# BSPD_5_Hank.net
KiCad netlist of a schematic drawn in EAGLE
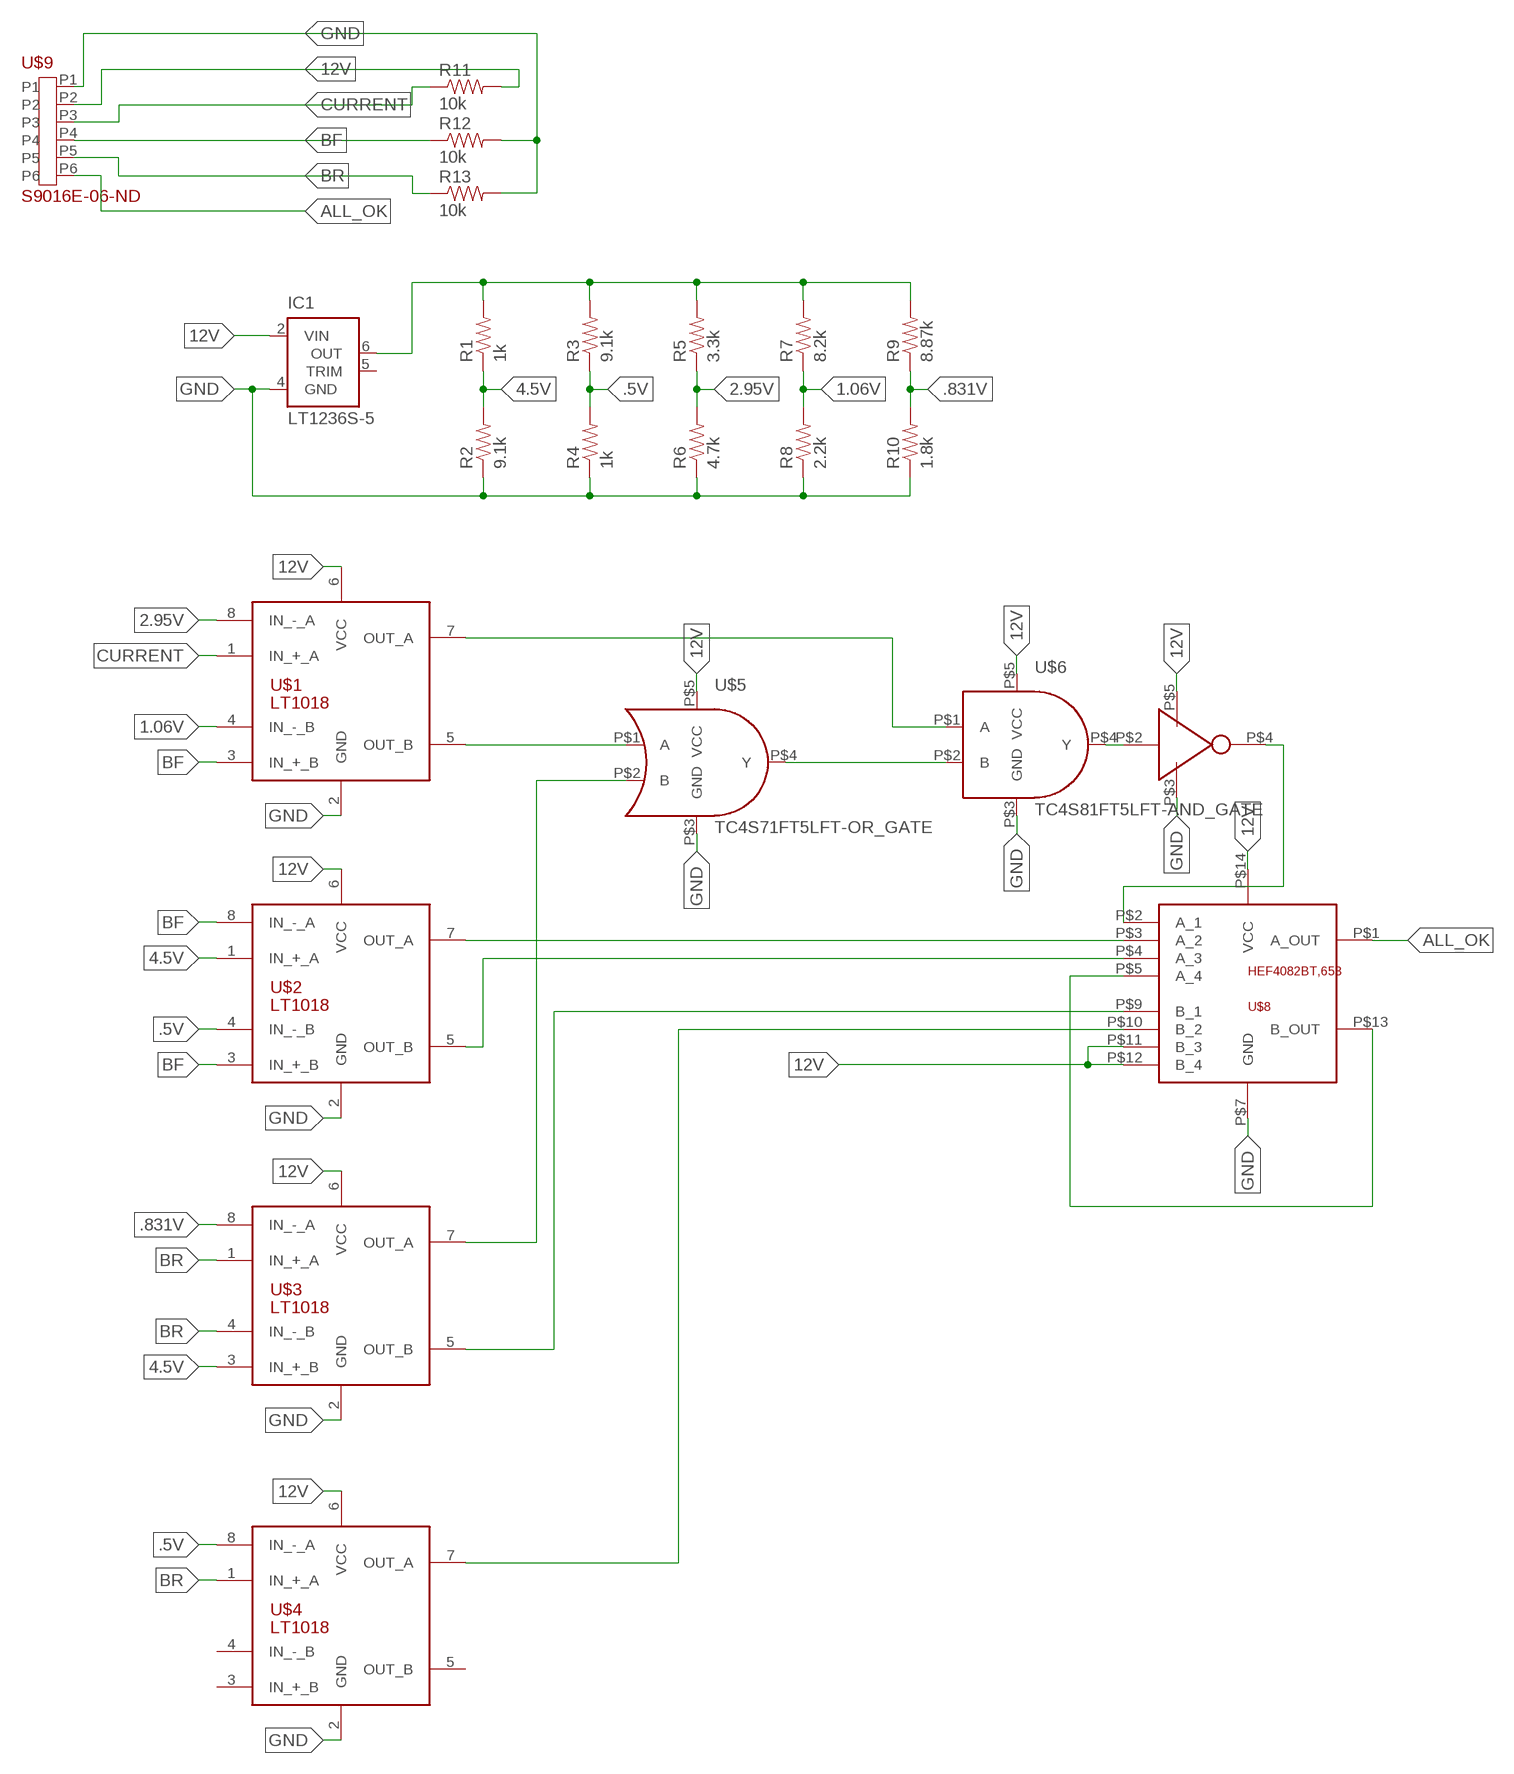
[diagram p0: schematic, sheet 1]

(export (version "E")
  (design (tool "Eeschema 10.0.6"))
  (components
    (comp (ref "IC1")
      (value "LT1236S-5")
      (footprint "eagle-import:SOIC8")
      (libsource (lib "eagle-import") (part "LT1236?S-5"))
    )
    (comp (ref "R1")
      (value "1k")
      (footprint "eagle-import:0603-RES")
      (libsource (lib "eagle-import") (part "RESISTOR0603"))
    )
    (comp (ref "R2")
      (value "9.1k")
      (footprint "eagle-import:0603-RES")
      (libsource (lib "eagle-import") (part "RESISTOR0603"))
    )
    (comp (ref "R3")
      (value "9.1k")
      (footprint "eagle-import:0603-RES")
      (libsource (lib "eagle-import") (part "RESISTOR0603"))
    )
    (comp (ref "R4")
      (value "1k")
      (footprint "eagle-import:0603-RES")
      (libsource (lib "eagle-import") (part "RESISTOR0603"))
    )
    (comp (ref "R5")
      (value "3.3k")
      (footprint "eagle-import:0603-RES")
      (libsource (lib "eagle-import") (part "RESISTOR0603"))
    )
    (comp (ref "R6")
      (value "4.7k")
      (footprint "eagle-import:0603-RES")
      (libsource (lib "eagle-import") (part "RESISTOR0603"))
    )
    (comp (ref "R7")
      (value "8.2k")
      (footprint "eagle-import:0603-RES")
      (libsource (lib "eagle-import") (part "RESISTOR0603"))
    )
    (comp (ref "R8")
      (value "2.2k")
      (footprint "eagle-import:0603-RES")
      (libsource (lib "eagle-import") (part "RESISTOR0603"))
    )
    (comp (ref "R9")
      (value "8.87k")
      (footprint "eagle-import:0603-RES")
      (libsource (lib "eagle-import") (part "RESISTOR0603"))
    )
    (comp (ref "R10")
      (value "1.8k")
      (footprint "eagle-import:0603-RES")
      (libsource (lib "eagle-import") (part "RESISTOR0603"))
    )
    (comp (ref "R11")
      (value "10k")
      (footprint "eagle-import:0603-RES")
      (libsource (lib "eagle-import") (part "RESISTOR0603"))
    )
    (comp (ref "R12")
      (value "10k")
      (footprint "eagle-import:0603-RES")
      (libsource (lib "eagle-import") (part "RESISTOR0603"))
    )
    (comp (ref "R13")
      (value "10k")
      (footprint "eagle-import:0603-RES")
      (libsource (lib "eagle-import") (part "RESISTOR0603"))
    )
    (comp (ref "U$1")
      (value "LT1018")
      (footprint "eagle-import:SOIC8")
      (libsource (lib "eagle-import") (part "LT1018"))
    )
    (comp (ref "U$2")
      (value "LT1018")
      (footprint "eagle-import:SOIC8")
      (libsource (lib "eagle-import") (part "LT1018"))
    )
    (comp (ref "U$3")
      (value "LT1018")
      (footprint "eagle-import:SOIC8")
      (libsource (lib "eagle-import") (part "LT1018"))
    )
    (comp (ref "U$4")
      (value "LT1018")
      (footprint "eagle-import:SOIC8")
      (libsource (lib "eagle-import") (part "LT1018"))
    )
    (comp (ref "U$5")
      (value "TC4S71FT5LFT-OR_GATE")
      (footprint "eagle-import:SSOP5-P-0.95")
      (libsource (lib "eagle-import") (part "TC4S71FT5LFT-OR_GATE"))
    )
    (comp (ref "U$6")
      (value "TC4S81FT5LFT-AND_GATE")
      (footprint "eagle-import:SSOP5-P-0.95")
      (libsource (lib "eagle-import") (part "TC4S81FT5LFT-AND_GATE"))
    )
    (comp (ref "U$7")
      (value "TC4S69F(TE85L,F)")
      (footprint "eagle-import:SSOP5-P-0.95")
      (libsource (lib "eagle-import") (part "TC4S69F(TE85L,F)"))
    )
    (comp (ref "U$8")
      (value "HEF4082BT,653")
      (footprint "eagle-import:NXP_14_SOIC")
      (libsource (lib "eagle-import") (part "HEF4082BT,653"))
    )
    (comp (ref "U$9")
      (value "S9016E-06-ND")
      (footprint "eagle-import:S9016E-05-ND")
      (libsource (lib "eagle-import") (part "S9016E-06-ND"))
    )
  )
  (nets
    (net (code "1") (name ".5V") (class "Default")
      (node (ref "R3") (pin "1") (pinfunction "1_1") (pintype "passive"))
      (node (ref "R4") (pin "2") (pinfunction "2_2") (pintype "passive"))
      (node (ref "U$2") (pin "4") (pinfunction "IN_-_B_4") (pintype "input"))
      (node (ref "U$4") (pin "8") (pinfunction "IN_-_A_8") (pintype "input"))
    )
    (net (code "2") (name ".831V") (class "Default")
      (node (ref "R10") (pin "2") (pinfunction "2_2") (pintype "passive"))
      (node (ref "R9") (pin "1") (pinfunction "1_1") (pintype "passive"))
      (node (ref "U$3") (pin "8") (pinfunction "IN_-_A_8") (pintype "input"))
    )
    (net (code "3") (name "1.06V") (class "Default")
      (node (ref "R7") (pin "1") (pinfunction "1_1") (pintype "passive"))
      (node (ref "R8") (pin "2") (pinfunction "2_2") (pintype "passive"))
      (node (ref "U$1") (pin "4") (pinfunction "IN_-_B_4") (pintype "input"))
    )
    (net (code "4") (name "2.95V") (class "Default")
      (node (ref "R5") (pin "1") (pinfunction "1_1") (pintype "passive"))
      (node (ref "R6") (pin "2") (pinfunction "2_2") (pintype "passive"))
      (node (ref "U$1") (pin "8") (pinfunction "IN_-_A_8") (pintype "input"))
    )
    (net (code "5") (name "4.5V") (class "Default")
      (node (ref "R1") (pin "1") (pinfunction "1_1") (pintype "passive"))
      (node (ref "R2") (pin "2") (pinfunction "2_2") (pintype "passive"))
      (node (ref "U$2") (pin "1") (pinfunction "IN_+_A_1") (pintype "input"))
      (node (ref "U$3") (pin "3") (pinfunction "IN_+_B_3") (pintype "input"))
    )
    (net (code "6") (name "12V") (class "Default")
      (node (ref "IC1") (pin "2") (pinfunction "VIN_2") (pintype "input"))
      (node (ref "R11") (pin "2") (pinfunction "2_2") (pintype "passive"))
      (node (ref "U$1") (pin "6") (pinfunction "VCC_6") (pintype "power_in"))
      (node (ref "U$2") (pin "6") (pinfunction "VCC_6") (pintype "power_in"))
      (node (ref "U$3") (pin "6") (pinfunction "VCC_6") (pintype "power_in"))
      (node (ref "U$4") (pin "6") (pinfunction "VCC_6") (pintype "power_in"))
      (node (ref "U$5") (pin "P$5") (pinfunction "VCC_P$5") (pintype "bidirectional"))
      (node (ref "U$6") (pin "P$5") (pinfunction "VCC_P$5") (pintype "bidirectional"))
      (node (ref "U$7") (pin "P$5") (pinfunction "VCC_P$5") (pintype "power_in"))
      (node (ref "U$8") (pin "P$11") (pinfunction "B_3_P$11") (pintype "open_collector"))
      (node (ref "U$8") (pin "P$12") (pinfunction "B_4_P$12") (pintype "open_collector"))
      (node (ref "U$8") (pin "P$14") (pinfunction "VCC_P$14") (pintype "power_in"))
      (node (ref "U$9") (pin "P2") (pinfunction "P2_P2") (pintype "bidirectional"))
    )
    (net (code "7") (name "ALL_OK") (class "Default")
      (node (ref "U$8") (pin "P$1") (pinfunction "A_OUT_P$1") (pintype "output"))
      (node (ref "U$9") (pin "P6") (pinfunction "P6_P6") (pintype "bidirectional"))
    )
    (net (code "8") (name "BF") (class "Default")
      (node (ref "R12") (pin "1") (pinfunction "1_1") (pintype "passive"))
      (node (ref "U$1") (pin "3") (pinfunction "IN_+_B_3") (pintype "input"))
      (node (ref "U$2") (pin "3") (pinfunction "IN_+_B_3") (pintype "input"))
      (node (ref "U$2") (pin "8") (pinfunction "IN_-_A_8") (pintype "input"))
      (node (ref "U$9") (pin "P4") (pinfunction "P4_P4") (pintype "bidirectional"))
    )
    (net (code "9") (name "BR") (class "Default")
      (node (ref "R13") (pin "1") (pinfunction "1_1") (pintype "passive"))
      (node (ref "U$3") (pin "1") (pinfunction "IN_+_A_1") (pintype "input"))
      (node (ref "U$3") (pin "4") (pinfunction "IN_-_B_4") (pintype "input"))
      (node (ref "U$4") (pin "1") (pinfunction "IN_+_A_1") (pintype "input"))
      (node (ref "U$9") (pin "P5") (pinfunction "P5_P5") (pintype "bidirectional"))
    )
    (net (code "10") (name "CURRENT") (class "Default")
      (node (ref "R11") (pin "1") (pinfunction "1_1") (pintype "passive"))
      (node (ref "U$1") (pin "1") (pinfunction "IN_+_A_1") (pintype "input"))
      (node (ref "U$9") (pin "P3") (pinfunction "P3_P3") (pintype "bidirectional"))
    )
    (net (code "11") (name "GND") (class "Default")
      (node (ref "IC1") (pin "4") (pinfunction "GND_4") (pintype "power_in"))
      (node (ref "R10") (pin "1") (pinfunction "1_1") (pintype "passive"))
      (node (ref "R12") (pin "2") (pinfunction "2_2") (pintype "passive"))
      (node (ref "R13") (pin "2") (pinfunction "2_2") (pintype "passive"))
      (node (ref "R2") (pin "1") (pinfunction "1_1") (pintype "passive"))
      (node (ref "R4") (pin "1") (pinfunction "1_1") (pintype "passive"))
      (node (ref "R6") (pin "1") (pinfunction "1_1") (pintype "passive"))
      (node (ref "R8") (pin "1") (pinfunction "1_1") (pintype "passive"))
      (node (ref "U$1") (pin "2") (pinfunction "GND_2") (pintype "power_in"))
      (node (ref "U$2") (pin "2") (pinfunction "GND_2") (pintype "power_in"))
      (node (ref "U$3") (pin "2") (pinfunction "GND_2") (pintype "power_in"))
      (node (ref "U$4") (pin "2") (pinfunction "GND_2") (pintype "power_in"))
      (node (ref "U$5") (pin "P$3") (pinfunction "GND_P$3") (pintype "bidirectional"))
      (node (ref "U$6") (pin "P$3") (pinfunction "GND_P$3") (pintype "bidirectional"))
      (node (ref "U$7") (pin "P$3") (pinfunction "GND_P$3") (pintype "power_in"))
      (node (ref "U$8") (pin "P$7") (pinfunction "GND_P$7") (pintype "power_in"))
      (node (ref "U$9") (pin "P1") (pinfunction "P1_P1") (pintype "bidirectional"))
    )
    (net (code "12") (name "Net-(IC1-OUT)") (class "Default")
      (node (ref "IC1") (pin "6") (pinfunction "OUT_6") (pintype "input"))
      (node (ref "R1") (pin "2") (pinfunction "2_2") (pintype "passive"))
      (node (ref "R3") (pin "2") (pinfunction "2_2") (pintype "passive"))
      (node (ref "R5") (pin "2") (pinfunction "2_2") (pintype "passive"))
      (node (ref "R7") (pin "2") (pinfunction "2_2") (pintype "passive"))
      (node (ref "R9") (pin "2") (pinfunction "2_2") (pintype "passive"))
    )
    (net (code "13") (name "Net-(U$1-OUT_A)") (class "Default")
      (node (ref "U$1") (pin "7") (pinfunction "OUT_A_7") (pintype "output"))
      (node (ref "U$6") (pin "P$1") (pinfunction "A_P$1") (pintype "bidirectional"))
    )
    (net (code "14") (name "Net-(U$1-OUT_B)") (class "Default")
      (node (ref "U$1") (pin "5") (pinfunction "OUT_B_5") (pintype "output"))
      (node (ref "U$5") (pin "P$1") (pinfunction "A_P$1") (pintype "bidirectional"))
    )
    (net (code "15") (name "Net-(U$2-OUT_A)") (class "Default")
      (node (ref "U$2") (pin "7") (pinfunction "OUT_A_7") (pintype "output"))
      (node (ref "U$8") (pin "P$3") (pinfunction "A_2_P$3") (pintype "open_collector"))
    )
    (net (code "16") (name "Net-(U$2-OUT_B)") (class "Default")
      (node (ref "U$2") (pin "5") (pinfunction "OUT_B_5") (pintype "output"))
      (node (ref "U$8") (pin "P$4") (pinfunction "A_3_P$4") (pintype "open_collector"))
    )
    (net (code "17") (name "Net-(U$3-OUT_A)") (class "Default")
      (node (ref "U$3") (pin "7") (pinfunction "OUT_A_7") (pintype "output"))
      (node (ref "U$5") (pin "P$2") (pinfunction "B_P$2") (pintype "bidirectional"))
    )
    (net (code "18") (name "Net-(U$3-OUT_B)") (class "Default")
      (node (ref "U$3") (pin "5") (pinfunction "OUT_B_5") (pintype "output"))
      (node (ref "U$8") (pin "P$9") (pinfunction "B_1_P$9") (pintype "open_collector"))
    )
    (net (code "19") (name "Net-(U$4-OUT_A)") (class "Default")
      (node (ref "U$4") (pin "7") (pinfunction "OUT_A_7") (pintype "output"))
      (node (ref "U$8") (pin "P$10") (pinfunction "B_2_P$10") (pintype "open_collector"))
    )
    (net (code "20") (name "Net-(U$5-Y)") (class "Default")
      (node (ref "U$5") (pin "P$4") (pinfunction "Y_P$4") (pintype "bidirectional"))
      (node (ref "U$6") (pin "P$2") (pinfunction "B_P$2") (pintype "bidirectional"))
    )
    (net (code "21") (name "Net-(U$6-Y)") (class "Default")
      (node (ref "U$6") (pin "P$4") (pinfunction "Y_P$4") (pintype "bidirectional"))
      (node (ref "U$7") (pin "P$2") (pinfunction "IN_P$2") (pintype "input"))
    )
    (net (code "22") (name "Net-(U$7-OUT)") (class "Default")
      (node (ref "U$7") (pin "P$4") (pinfunction "OUT_P$4") (pintype "output"))
      (node (ref "U$8") (pin "P$2") (pinfunction "A_1_P$2") (pintype "open_collector"))
    )
    (net (code "23") (name "Net-(U$8-A_4)") (class "Default")
      (node (ref "U$8") (pin "P$13") (pinfunction "B_OUT_P$13") (pintype "output"))
      (node (ref "U$8") (pin "P$5") (pinfunction "A_4_P$5") (pintype "open_collector"))
    )
    (net (code "24") (name "unconnected-(IC1-TRIM-Pad5)") (class "Default")
      (node (ref "IC1") (pin "5") (pinfunction "TRIM_5") (pintype "passive"))
    )
    (net (code "25") (name "unconnected-(U$4-IN_+_B-Pad3)") (class "Default")
      (node (ref "U$4") (pin "3") (pinfunction "IN_+_B_3") (pintype "input"))
    )
    (net (code "26") (name "unconnected-(U$4-IN_-_B-Pad4)") (class "Default")
      (node (ref "U$4") (pin "4") (pinfunction "IN_-_B_4") (pintype "input"))
    )
    (net (code "27") (name "unconnected-(U$4-OUT_B-Pad5)") (class "Default")
      (node (ref "U$4") (pin "5") (pinfunction "OUT_B_5") (pintype "output"))
    )
  )
)
